# lead_acid_charger.net
KiCad netlist of a schematic drawn in EAGLE
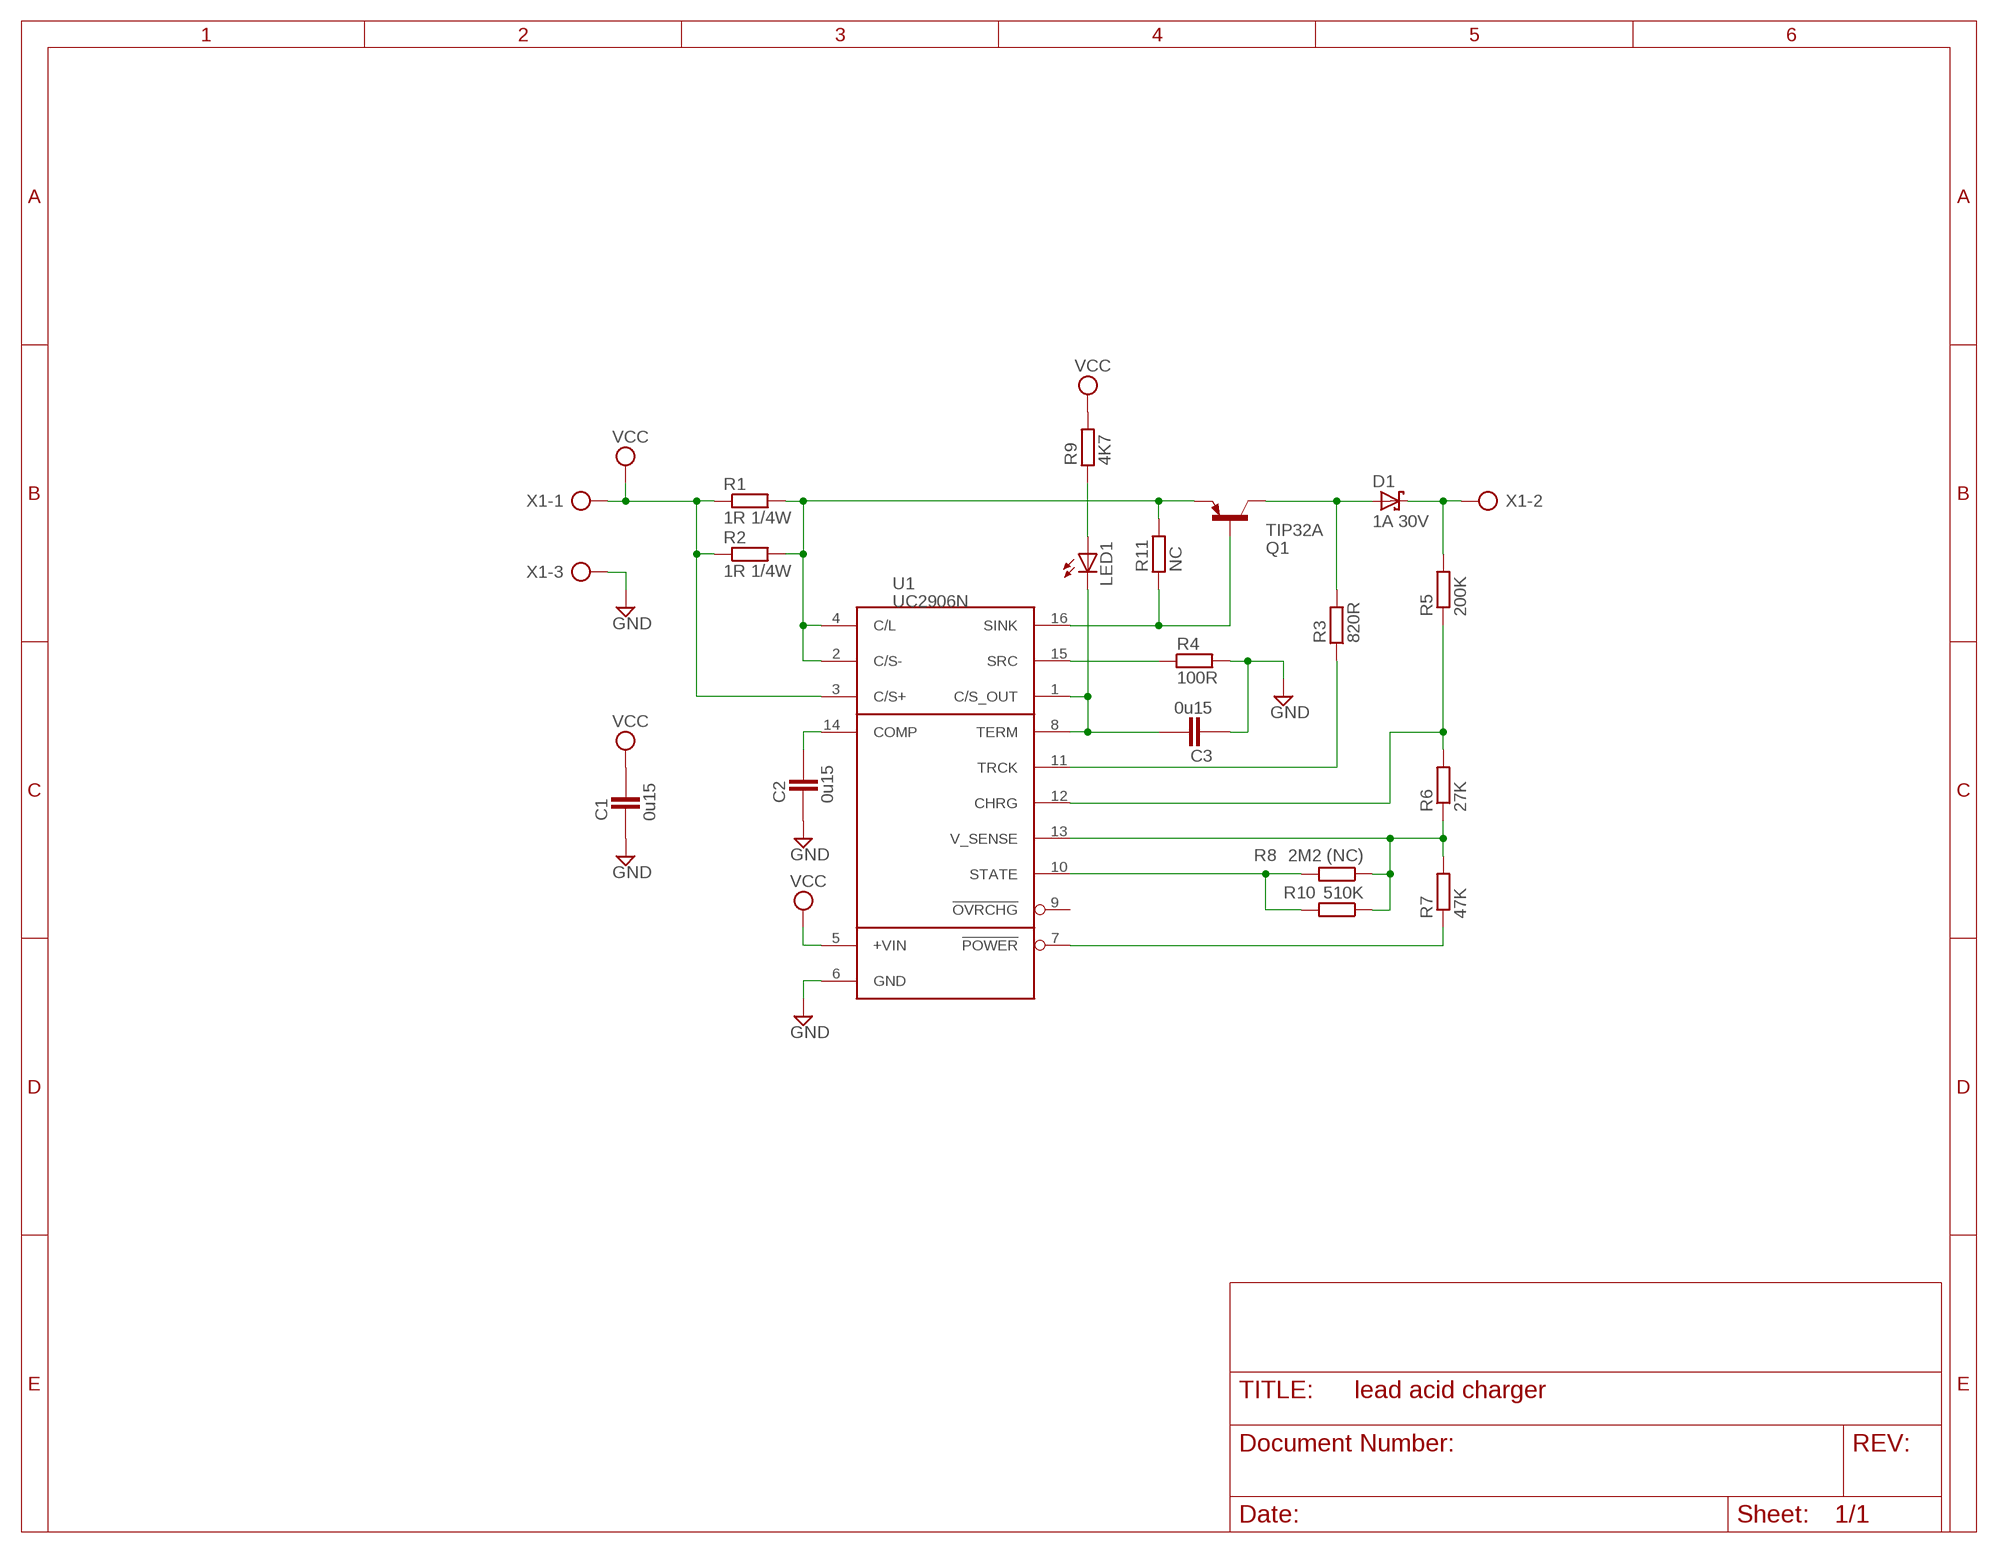
[diagram p0: schematic, sheet 1]

(export (version "E")
  (design (tool "Eeschema 10.0.6"))
  (components
    (comp (ref "C1")
      (value "0u15")
      (footprint "eagle-import:CAP2012X70N")
      (libsource (lib "eagle-import") (part "CAPACITOR_0805N"))
    )
    (comp (ref "C2")
      (value "0u15")
      (footprint "eagle-import:CAP2012X70N")
      (libsource (lib "eagle-import") (part "CAPACITOR_0805N"))
    )
    (comp (ref "C3")
      (value "0u15")
      (footprint "eagle-import:CAP2012X70N")
      (libsource (lib "eagle-import") (part "CAPACITOR_0805N"))
    )
    (comp (ref "D1")
      (value "1A 30V")
      (footprint "eagle-import:DIOM5436X265N")
      (libsource (lib "eagle-import") (part "SCHOTTKY_SMB"))
    )
    (comp (ref "LED1")
      (value "LED3MM")
      (footprint "eagle-import:LED3MM")
      (libsource (lib "eagle-import") (part "LED3MM"))
    )
    (comp (ref "Q1")
      (value "TIP32A")
      (footprint "eagle-import:TO220")
      (libsource (lib "eagle-import") (part "TIP30"))
    )
    (comp (ref "R1")
      (value "1R 1/4W")
      (footprint "eagle-import:0207_10")
      (libsource (lib "eagle-import") (part "R-EU_0207/10"))
    )
    (comp (ref "R2")
      (value "1R 1/4W")
      (footprint "eagle-import:0207_10")
      (libsource (lib "eagle-import") (part "R-EU_0207/10"))
    )
    (comp (ref "R3")
      (value "820R")
      (footprint "eagle-import:RESC3115X70N")
      (libsource (lib "eagle-import") (part "RESISTOR_1206"))
    )
    (comp (ref "R4")
      (value "100R")
      (footprint "eagle-import:RESC2012X70N")
      (libsource (lib "eagle-import") (part "RESISTOR_0805"))
    )
    (comp (ref "R5")
      (value "200K")
      (footprint "eagle-import:0207_10")
      (libsource (lib "eagle-import") (part "R-EU_0207/10"))
    )
    (comp (ref "R6")
      (value "27K")
      (footprint "eagle-import:0207_10")
      (libsource (lib "eagle-import") (part "R-EU_0207/10"))
    )
    (comp (ref "R7")
      (value "47K")
      (footprint "eagle-import:0207_10")
      (libsource (lib "eagle-import") (part "R-EU_0207/10"))
    )
    (comp (ref "R8")
      (value "2M2 (NC)")
      (footprint "eagle-import:0207_10")
      (libsource (lib "eagle-import") (part "R-EU_0207/10"))
    )
    (comp (ref "R9")
      (value "4K7")
      (footprint "eagle-import:RESC2012X70N")
      (libsource (lib "eagle-import") (part "RESISTOR_0805"))
    )
    (comp (ref "R10")
      (value "510K")
      (footprint "eagle-import:0207_10")
      (libsource (lib "eagle-import") (part "R-EU_0207/10"))
    )
    (comp (ref "R11")
      (value "NC")
      (footprint "eagle-import:RESC1608X55N")
      (libsource (lib "eagle-import") (part "RESISTOR_0603"))
    )
    (comp (ref "U1")
      (value "UC2906N")
      (footprint "eagle-import:DIL16")
      (libsource (lib "eagle-import") (part "UC2906N"))
    )
    (comp (ref "X1")
      (value "AK500/3")
      (footprint "eagle-import:AK500-3")
      (libsource (lib "eagle-import") (part "AK500/3"))
    )
  )
  (nets
    (net (code "1") (name "GND") (class "Default")
      (node (ref "C1") (pin "1") (pinfunction "1_1") (pintype "passive"))
      (node (ref "C2") (pin "1") (pinfunction "1_1") (pintype "passive"))
      (node (ref "C3") (pin "1") (pinfunction "1_1") (pintype "passive"))
      (node (ref "R4") (pin "2") (pinfunction "2_2") (pintype "passive"))
      (node (ref "U1") (pin "6") (pinfunction "GND_6") (pintype "input"))
      (node (ref "X1") (pin "3") (pinfunction "KL_3") (pintype "passive"))
    )
    (net (code "2") (name "Net-(LED1-C)") (class "Default")
      (node (ref "C3") (pin "2") (pinfunction "2_2") (pintype "passive"))
      (node (ref "LED1") (pin "K") (pinfunction "C_K") (pintype "passive"))
      (node (ref "U1") (pin "1") (pinfunction "C/S_OUT_1") (pintype "output"))
      (node (ref "U1") (pin "8") (pinfunction "TERM_8") (pintype "input"))
    )
    (net (code "3") (name "Net-(LED1-PadA)") (class "Default")
      (node (ref "LED1") (pin "A") (pinfunction "A_A") (pintype "passive"))
      (node (ref "R9") (pin "1") (pinfunction "1_1") (pintype "passive"))
    )
    (net (code "4") (name "Net-(Q1-B)") (class "Default")
      (node (ref "Q1") (pin "1") (pinfunction "B_1") (pintype "passive"))
      (node (ref "R11") (pin "1") (pinfunction "1_1") (pintype "passive"))
      (node (ref "U1") (pin "16") (pinfunction "SINK_16") (pintype "bidirectional"))
    )
    (net (code "5") (name "Net-(Q1-C)") (class "Default")
      (node (ref "D1") (pin "A") (pinfunction "A_A") (pintype "passive"))
      (node (ref "Q1") (pin "2") (pinfunction "C_2") (pintype "passive"))
      (node (ref "R3") (pin "2") (pinfunction "2_2") (pintype "passive"))
    )
    (net (code "6") (name "Net-(Q1-E)") (class "Default")
      (node (ref "Q1") (pin "3") (pinfunction "E_3") (pintype "passive"))
      (node (ref "R1") (pin "2") (pinfunction "2_2") (pintype "passive"))
      (node (ref "R11") (pin "2") (pinfunction "2_2") (pintype "passive"))
      (node (ref "R2") (pin "2") (pinfunction "2_2") (pintype "passive"))
      (node (ref "U1") (pin "2") (pinfunction "C/S-_2") (pintype "input"))
      (node (ref "U1") (pin "4") (pinfunction "C/L_4") (pintype "input"))
    )
    (net (code "7") (name "Net-(U1-CHRG)") (class "Default")
      (node (ref "R5") (pin "1") (pinfunction "1_1") (pintype "passive"))
      (node (ref "R6") (pin "2") (pinfunction "2_2") (pintype "passive"))
      (node (ref "U1") (pin "12") (pinfunction "CHRG_12") (pintype "output"))
    )
    (net (code "8") (name "Net-(U1-COMP)") (class "Default")
      (node (ref "C2") (pin "2") (pinfunction "2_2") (pintype "passive"))
      (node (ref "U1") (pin "14") (pinfunction "COMP_14") (pintype "bidirectional"))
    )
    (net (code "9") (name "Net-(U1-SRC)") (class "Default")
      (node (ref "R4") (pin "1") (pinfunction "1_1") (pintype "passive"))
      (node (ref "U1") (pin "15") (pinfunction "SRC_15") (pintype "bidirectional"))
    )
    (net (code "10") (name "Net-(U1-STATE)") (class "Default")
      (node (ref "R10") (pin "2") (pinfunction "2_2") (pintype "passive"))
      (node (ref "R8") (pin "2") (pinfunction "2_2") (pintype "passive"))
      (node (ref "U1") (pin "10") (pinfunction "STATE_10") (pintype "output"))
    )
    (net (code "11") (name "Net-(U1-TRCK)") (class "Default")
      (node (ref "R3") (pin "1") (pinfunction "1_1") (pintype "passive"))
      (node (ref "U1") (pin "11") (pinfunction "TRCK_11") (pintype "output"))
    )
    (net (code "12") (name "Net-(U1-V_SENSE)") (class "Default")
      (node (ref "R10") (pin "1") (pinfunction "1_1") (pintype "passive"))
      (node (ref "R6") (pin "1") (pinfunction "1_1") (pintype "passive"))
      (node (ref "R7") (pin "2") (pinfunction "2_2") (pintype "passive"))
      (node (ref "R8") (pin "1") (pinfunction "1_1") (pintype "passive"))
      (node (ref "U1") (pin "13") (pinfunction "V_SENSE_13") (pintype "input"))
    )
    (net (code "13") (name "Net-(U1-~{POWER})") (class "Default")
      (node (ref "R7") (pin "1") (pinfunction "1_1") (pintype "passive"))
      (node (ref "U1") (pin "7") (pinfunction "~{POWER}_7") (pintype "output"))
    )
    (net (code "14") (name "Net-(X1B-KL)") (class "Default")
      (node (ref "D1") (pin "K") (pinfunction "K_K") (pintype "passive"))
      (node (ref "R5") (pin "2") (pinfunction "2_2") (pintype "passive"))
      (node (ref "X1") (pin "2") (pinfunction "KL_2") (pintype "passive"))
    )
    (net (code "15") (name "VCC") (class "Default")
      (node (ref "C1") (pin "2") (pinfunction "2_2") (pintype "passive"))
      (node (ref "R1") (pin "1") (pinfunction "1_1") (pintype "passive"))
      (node (ref "R2") (pin "1") (pinfunction "1_1") (pintype "passive"))
      (node (ref "R9") (pin "2") (pinfunction "2_2") (pintype "passive"))
      (node (ref "U1") (pin "3") (pinfunction "C/S+_3") (pintype "input"))
      (node (ref "U1") (pin "5") (pinfunction "+VIN_5") (pintype "input"))
      (node (ref "X1") (pin "1") (pinfunction "KL_1") (pintype "passive"))
    )
    (net (code "16") (name "unconnected-(U1-~{OVRCHG}-Pad9)") (class "Default")
      (node (ref "U1") (pin "9") (pinfunction "~{OVRCHG}_9") (pintype "output"))
    )
  )
)
